# top.net
KiCad netlist of a schematic drawn in Altium Designer
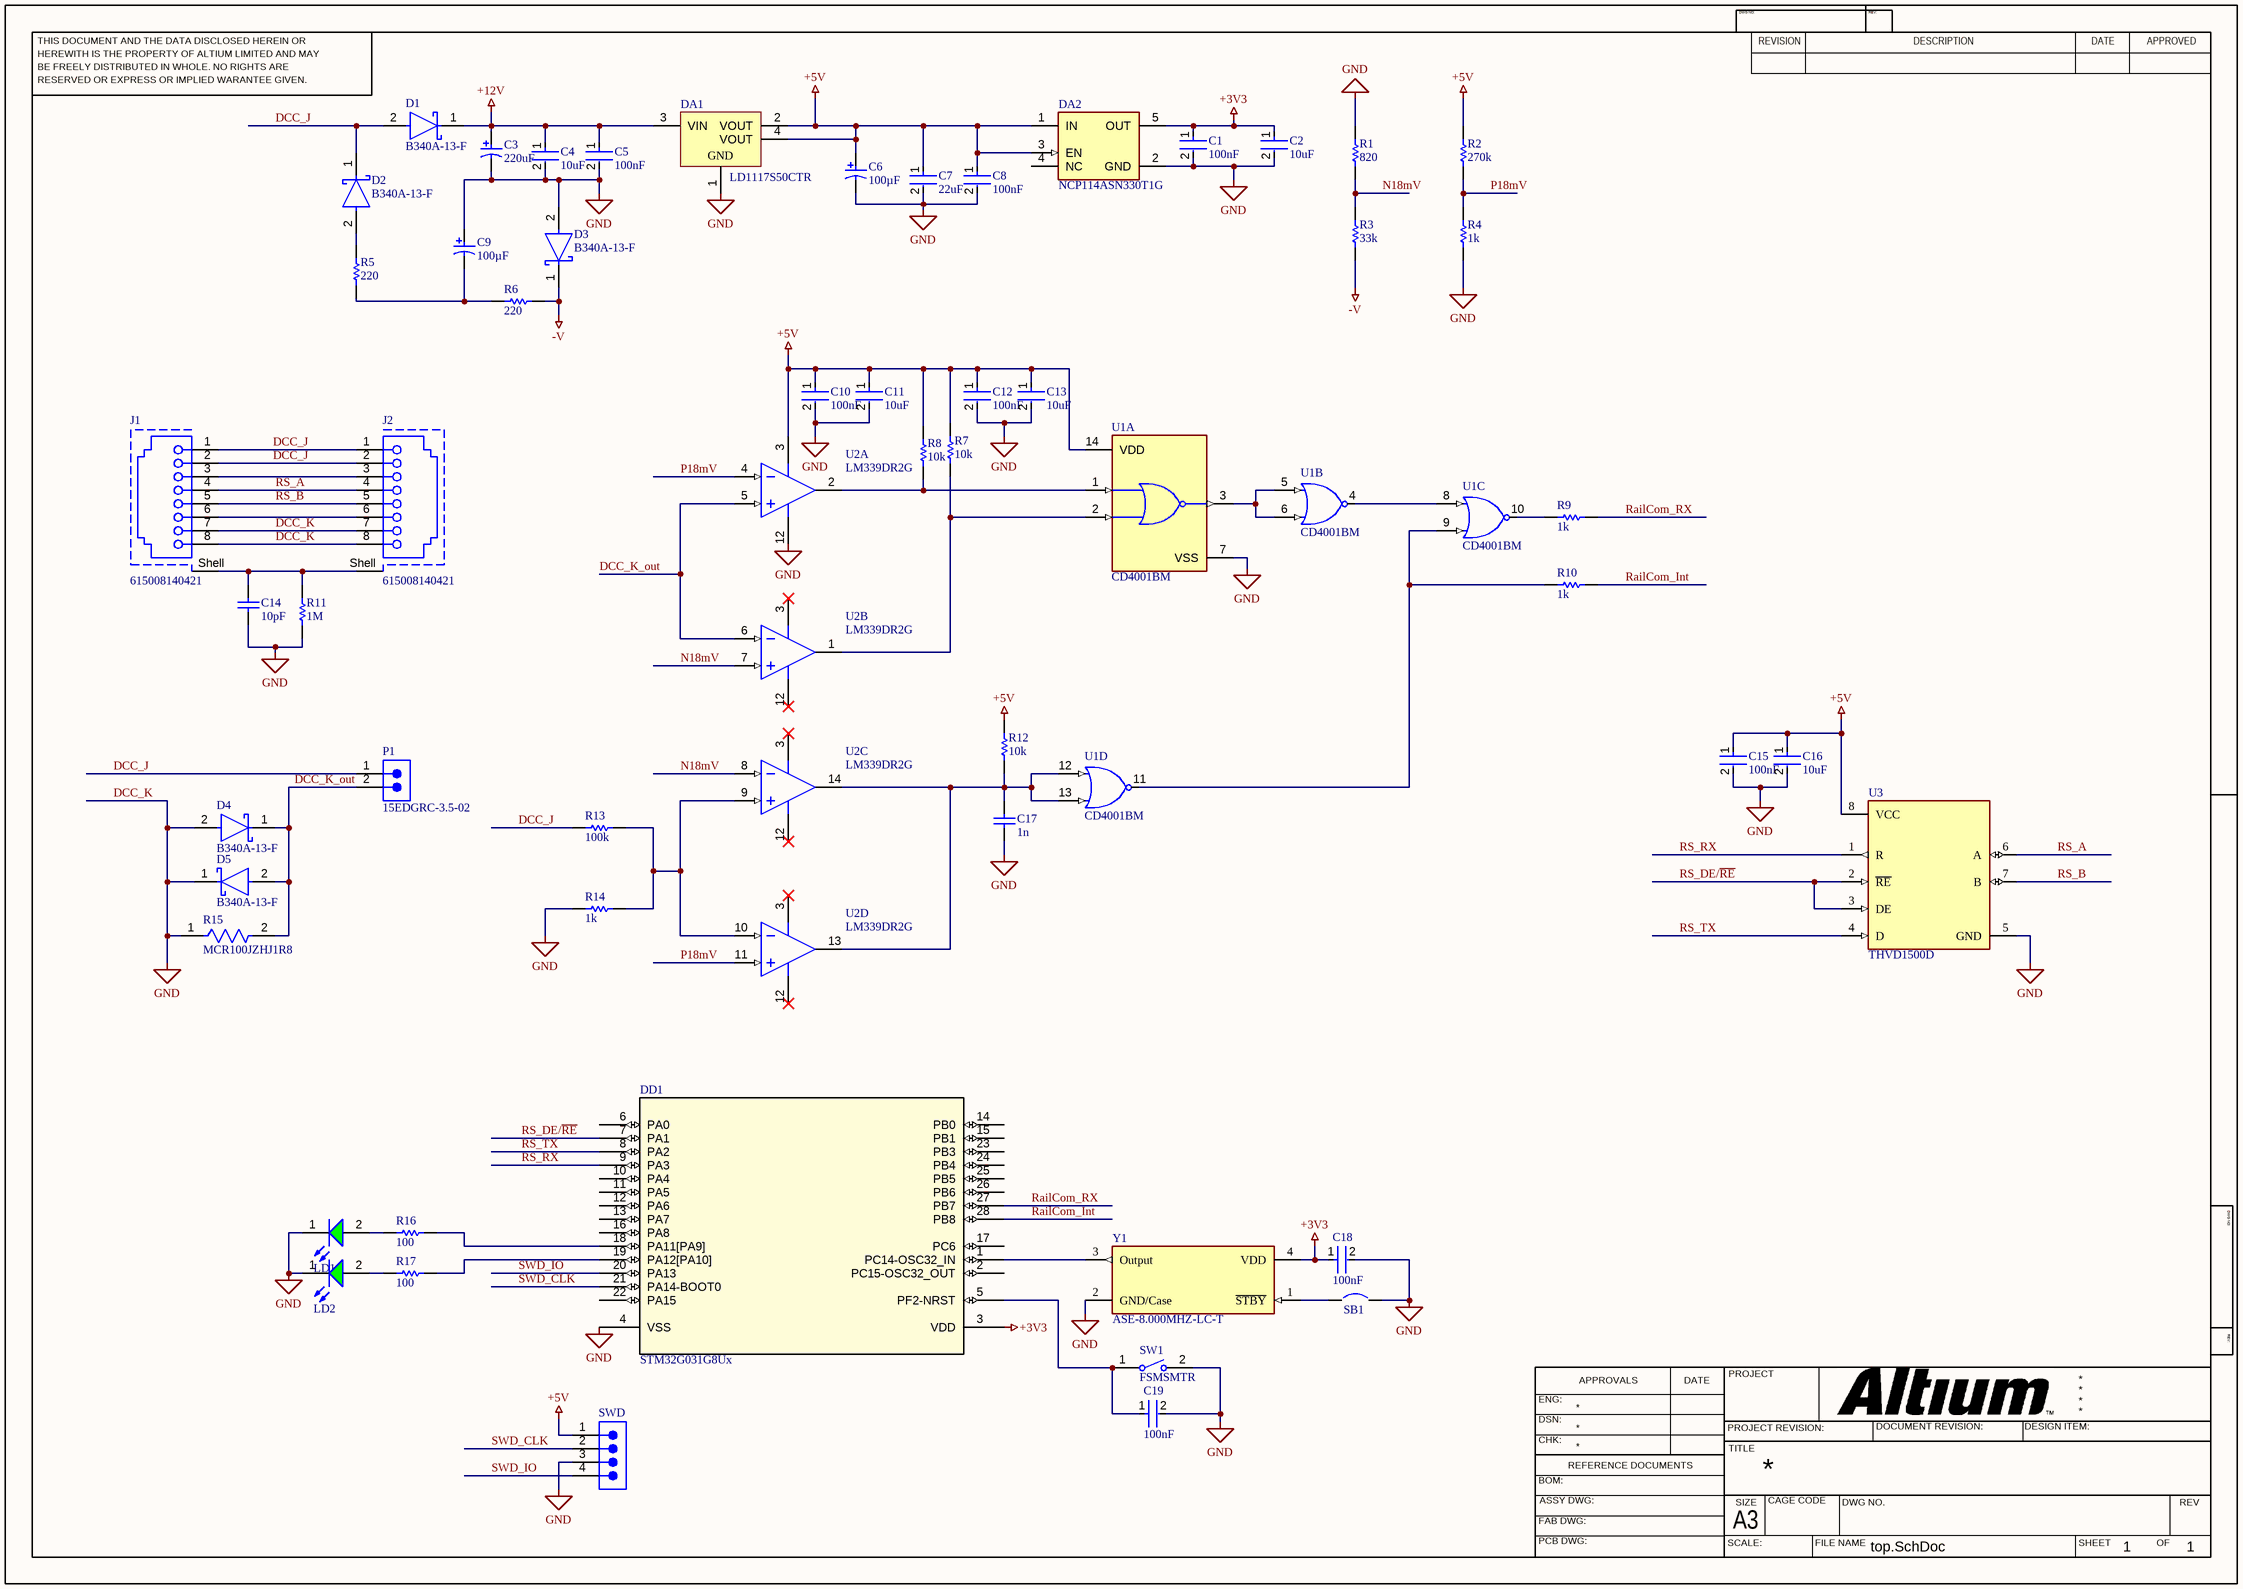
[diagram p0: top.SchDoc]

(export (version "E")
  (design (tool "Eeschema 10.0.6"))
  (components
    (comp (ref "C1")
      (value "CGA3E2X7R1H104K080AA")
      (footprint "FP-CGA3E-0_3-0_1-IPC_C")
      (description "Cap Ceramic 100nF 50V X7R 10% Pad SMD 0603 +125°C Automotive T/R")
      (fields
        (field (name "TOLERANCE") "10%")
        (field (name "CAPACITANCE") "100nF")
        (field (name "VOLTAGE") "50V")
      )
      (libsource (lib "Altium Content Vault") (part "b4654b650e69147ec39a6b967a45e02"))
    )
    (comp (ref "C2")
      (value "GRM188R60J106ME47D")
      (footprint "FP-GRM188-0_1-e0_2_0_55-IPC_C")
      (description "Chip Multilayer Ceramic Capacitors for General Purpose, 0603, 10uF, X5R, 15%, 20%, 6.3V")
      (fields
        (field (name "CAPACITANCE") "10uF")
        (field (name "VOLTAGE") "6.3V")
        (field (name "TOLERANCE") "20%")
      )
      (libsource (lib "Altium Content Vault") (part "02cd4be3c70576c341d710602a673aa"))
    )
    (comp (ref "C3")
      (value "220uF")
      (footprint "PNSC-EEE-FK1E221P_N")
      (fields (field (name "MANUFACTURER") "Panasonic") (field (name "Comment") "EEE-FK1E221P"))
      (libsource (lib "Altium Content Vault") (part "CAP-P-2"))
    )
    (comp (ref "C4")
      (value "GRM188R60J106ME47D")
      (footprint "FP-GRM188-0_1-e0_2_0_55-IPC_C")
      (description "Chip Multilayer Ceramic Capacitors for General Purpose, 0603, 10uF, X5R, 15%, 20%, 6.3V")
      (fields
        (field (name "CAPACITANCE") "10uF")
        (field (name "VOLTAGE") "6.3V")
        (field (name "TOLERANCE") "20%")
      )
      (libsource (lib "Altium Content Vault") (part "02cd4be3c70576c341d710602a673aa"))
    )
    (comp (ref "C5")
      (value "CGA3E2X7R1H104K080AA")
      (footprint "FP-CGA3E-0_3-0_1-IPC_C")
      (description "Cap Ceramic 100nF 50V X7R 10% Pad SMD 0603 +125°C Automotive T/R")
      (fields
        (field (name "TOLERANCE") "10%")
        (field (name "CAPACITANCE") "100nF")
        (field (name "VOLTAGE") "50V")
      )
      (libsource (lib "Altium Content Vault") (part "b4654b650e69147ec39a6b967a45e02"))
    )
    (comp (ref "C6")
      (value "EEEFK1E101XP")
      (footprint "PNSC-FK-V-D8_V")
      (fields (field (name "CAPACITANCE") "100µF") (field (name "MANUFACTURER") "Panasonic"))
      (libsource (lib "Altium Content Vault") (part "CAP-P-2"))
    )
    (comp (ref "C7")
      (value "GRM188R61A226ME15D")
      (footprint "FP-GRM188-0_2-IPC_C")
      (description "Chip Multilayer Ceramic Capacitors for General Purpose, 0603, 22uF, X5R, 15%, 20%, 10V")
      (fields (field (name "TOLERANCE") "20%") (field (name "CAPACITANCE") "22uF"))
      (libsource (lib "Altium Content Vault") (part "11868f565c42a9108669ba33697ecf6"))
    )
    (comp (ref "C8")
      (value "CGA3E2X7R1H104K080AA")
      (footprint "FP-CGA3E-0_3-0_1-IPC_C")
      (description "Cap Ceramic 100nF 50V X7R 10% Pad SMD 0603 +125°C Automotive T/R")
      (fields
        (field (name "TOLERANCE") "10%")
        (field (name "CAPACITANCE") "100nF")
        (field (name "VOLTAGE") "50V")
      )
      (libsource (lib "Altium Content Vault") (part "b4654b650e69147ec39a6b967a45e02"))
    )
    (comp (ref "C9")
      (value "EEEFK1E101XP")
      (footprint "PNSC-FK-V-D8_V")
      (fields (field (name "CAPACITANCE") "100µF") (field (name "MANUFACTURER") "Panasonic"))
      (libsource (lib "Altium Content Vault") (part "CAP-P-2"))
    )
    (comp (ref "C10")
      (value "CGA3E2X7R1H104K080AA")
      (footprint "FP-CGA3E-0_3-0_1-IPC_C")
      (description "Cap Ceramic 100nF 50V X7R 10% Pad SMD 0603 +125°C Automotive T/R")
      (fields
        (field (name "TOLERANCE") "10%")
        (field (name "CAPACITANCE") "100nF")
        (field (name "VOLTAGE") "50V")
      )
      (libsource (lib "Altium Content Vault") (part "b4654b650e69147ec39a6b967a45e02"))
    )
    (comp (ref "C11")
      (value "GRM188R60J106ME47D")
      (footprint "FP-GRM188-0_1-e0_2_0_55-IPC_C")
      (description "Chip Multilayer Ceramic Capacitors for General Purpose, 0603, 10uF, X5R, 15%, 20%, 6.3V")
      (fields
        (field (name "CAPACITANCE") "10uF")
        (field (name "VOLTAGE") "6.3V")
        (field (name "TOLERANCE") "20%")
      )
      (libsource (lib "Altium Content Vault") (part "02cd4be3c70576c341d710602a673aa"))
    )
    (comp (ref "C12")
      (value "CGA3E2X7R1H104K080AA")
      (footprint "FP-CGA3E-0_3-0_1-IPC_C")
      (description "Cap Ceramic 100nF 50V X7R 10% Pad SMD 0603 +125°C Automotive T/R")
      (fields
        (field (name "TOLERANCE") "10%")
        (field (name "CAPACITANCE") "100nF")
        (field (name "VOLTAGE") "50V")
      )
      (libsource (lib "Altium Content Vault") (part "b4654b650e69147ec39a6b967a45e02"))
    )
    (comp (ref "C13")
      (value "GRM188R60J106ME47D")
      (footprint "FP-GRM188-0_1-e0_2_0_55-IPC_C")
      (description "Chip Multilayer Ceramic Capacitors for General Purpose, 0603, 10uF, X5R, 15%, 20%, 6.3V")
      (fields
        (field (name "CAPACITANCE") "10uF")
        (field (name "VOLTAGE") "6.3V")
        (field (name "TOLERANCE") "20%")
      )
      (libsource (lib "Altium Content Vault") (part "02cd4be3c70576c341d710602a673aa"))
    )
    (comp (ref "C14")
      (value "10pF")
      (footprint "CAPC0603(1608)100_N")
      (description "CAP 10pF 25V ±1% 0603 (1608 Metric) Thickness 1mm SMD")
      (fields (field (name "TOLERANCE") "Â±1%") (field (name "Comment") "CAP 10pF 25V 0603(1608)"))
      (libsource (lib "Altium Content Vault") (part "CAP"))
    )
    (comp (ref "C15")
      (value "CGA3E2X7R1H104K080AA")
      (footprint "FP-CGA3E-0_3-0_1-IPC_C")
      (description "Cap Ceramic 100nF 50V X7R 10% Pad SMD 0603 +125°C Automotive T/R")
      (fields
        (field (name "TOLERANCE") "10%")
        (field (name "CAPACITANCE") "100nF")
        (field (name "VOLTAGE") "50V")
      )
      (libsource (lib "Altium Content Vault") (part "b4654b650e69147ec39a6b967a45e02"))
    )
    (comp (ref "C16")
      (value "GRM188R60J106ME47D")
      (footprint "FP-GRM188-0_1-e0_2_0_55-IPC_C")
      (description "Chip Multilayer Ceramic Capacitors for General Purpose, 0603, 10uF, X5R, 15%, 20%, 6.3V")
      (fields
        (field (name "CAPACITANCE") "10uF")
        (field (name "VOLTAGE") "6.3V")
        (field (name "TOLERANCE") "20%")
      )
      (libsource (lib "Altium Content Vault") (part "02cd4be3c70576c341d710602a673aa"))
    )
    (comp (ref "C17")
      (value "1n")
      (footprint "CAPC1608X90X35NL10T15")
      (fields (field (name "PART NUMBER") "GRM188R71H102KA01D") (field (name "MANUFACTURER") "Murata"))
      (libsource (lib "Altium Content Vault") (part "CAP"))
    )
    (comp (ref "C18")
      (value "CGA3E2X7R1H104K080AA")
      (footprint "FP-CGA3E-0_3-0_1-IPC_C")
      (description "Cap Ceramic 100nF 50V X7R 10% Pad SMD 0603 +125°C Automotive T/R")
      (fields
        (field (name "TOLERANCE") "10%")
        (field (name "CAPACITANCE") "100nF")
        (field (name "VOLTAGE") "50V")
      )
      (libsource (lib "Altium Content Vault") (part "b4654b650e69147ec39a6b967a45e02"))
    )
    (comp (ref "C19")
      (value "CGA3E2X7R1H104K080AA")
      (footprint "FP-CGA3E-0_3-0_1-IPC_C")
      (description "Cap Ceramic 100nF 50V X7R 10% Pad SMD 0603 +125°C Automotive T/R")
      (fields
        (field (name "TOLERANCE") "10%")
        (field (name "CAPACITANCE") "100nF")
        (field (name "VOLTAGE") "50V")
      )
      (libsource (lib "Altium Content Vault") (part "b4654b650e69147ec39a6b967a45e02"))
    )
    (comp (ref "D1")
      (value "B340A-13-F")
      (footprint "FP-SMA-MFG")
      (description "DIODE SCHOTTKY 40V 3A SMA")
      (fields (field (name "VOLTAGE") "40V"))
      (libsource (lib "Altium Content Vault") (part "1d6ec82d83fb6aee721767c19dac4b9"))
    )
    (comp (ref "D2")
      (value "B340A-13-F")
      (footprint "FP-SMA-MFG")
      (description "DIODE SCHOTTKY 40V 3A SMA")
      (fields (field (name "VOLTAGE") "40V"))
      (libsource (lib "Altium Content Vault") (part "1d6ec82d83fb6aee721767c19dac4b9"))
    )
    (comp (ref "D3")
      (value "B340A-13-F")
      (footprint "FP-SMA-MFG")
      (description "DIODE SCHOTTKY 40V 3A SMA")
      (fields (field (name "VOLTAGE") "40V"))
      (libsource (lib "Altium Content Vault") (part "1d6ec82d83fb6aee721767c19dac4b9"))
    )
    (comp (ref "D4")
      (value "B340A-13-F")
      (footprint "FP-SMA-MFG")
      (description "DIODE SCHOTTKY 40V 3A SMA")
      (fields (field (name "VOLTAGE") "40V"))
      (libsource (lib "Altium Content Vault") (part "1d6ec82d83fb6aee721767c19dac4b9"))
    )
    (comp (ref "D5")
      (value "B340A-13-F")
      (footprint "FP-SMA-MFG")
      (description "DIODE SCHOTTKY 40V 3A SMA")
      (fields (field (name "VOLTAGE") "40V"))
      (libsource (lib "Altium Content Vault") (part "1d6ec82d83fb6aee721767c19dac4b9"))
    )
    (comp (ref "DA1")
      (value "LD1117S50CTR")
      (footprint "SOT-223_N")
      (description "Fixed Low Drop Positive Voltage Regulator, 5V, 4-Pin SOT-223, Tape and Reel")
      (libsource (lib "Altium Content Vault") (part "PM-REG-LD1117-SOT4"))
    )
    (comp (ref "DA2")
      (value "NCP114ASN330T1G")
      (footprint "FP-483-MFG")
      (description "IC REG LINEAR 3.3V 300MA 5TSOP")
      (fields
        (field (name "MANUFACTURER") "ON Semiconductor")
        (field (name "OCTOPART") "https://octopart.com/ncp114asn330t1g-on+semiconductor-74628742")
      )
      (libsource (lib "Altium Content Vault") (part "57814aa37072aacea77ef0fe9350350"))
    )
    (comp (ref "DD1")
      (value "STM32G031G8Ux")
      (footprint "UFQFPN-28")
      (fields
        (field (name "MANUFACTURER_PART_NUMBER") "stm32g0_ufqfpn28_t1")
        (field (name "COPYRIGHT") "Copyright (C) 2016 Accelerated Designs. All rights reserved")
      )
      (libsource (lib "ST Microelectronics STM32 G0") (part "STM32G031G8Ux"))
    )
    (comp (ref "J1")
      (value "615008140421")
      (footprint "615008140421")
      (libsource (lib "Altium Content Vault") (part "8P8C - 1 Port - Shielded"))
    )
    (comp (ref "J2")
      (value "615008140421")
      (footprint "615008140421")
      (libsource (lib "Altium Content Vault") (part "8P8C - 1 Port - Shielded"))
    )
    (comp (ref "LD1")
      (value "150060VS75000")
      (footprint "WL-SMCW_0603_150060xx75000")
      (description "WURTH ELEKTRONIK - 150060VS75000 - LED, Green, SMD, 0603, 30 mA, 2 V, 570 nm")
      (libsource (lib "Altium Content Vault") (part "LED_Green_2A-1K"))
    )
    (comp (ref "LD2")
      (value "150060VS75000")
      (footprint "WL-SMCW_0603_150060xx75000")
      (description "WURTH ELEKTRONIK - 150060VS75000 - LED, Green, SMD, 0603, 30 mA, 2 V, 570 nm")
      (libsource (lib "Altium Content Vault") (part "LED_Green_2A-1K"))
    )
    (comp (ref "P1")
      (value "15EDGRC-3.5-02")
      (footprint "691305140002")
      (libsource (lib "Altium Content Vault") (part "TBL - 1R - 02P - Male"))
    )
    (comp (ref "R1")
      (value "820")
      (footprint "RESC1608X55X30ML15T15")
      (fields (field (name "MANUFACTURER") "Panasonic") (field (name "PART NUMBER") "ERJ3EKF8203V"))
      (libsource (lib "Altium Content Vault") (part "RES"))
    )
    (comp (ref "R2")
      (value "270k")
      (footprint "RESC0603X26X15LL03T05")
      (fields (field (name "PART NUMBER") "ERJ1GNF2703C") (field (name "MANUFACTURER") "Panasonic"))
      (libsource (lib "Altium Content Vault") (part "RES"))
    )
    (comp (ref "R3")
      (value "33k")
      (footprint "RESC1608X55X30ML20T20")
      (fields (field (name "PART NUMBER") "ERA3AEB333V") (field (name "MANUFACTURER") "Panasonic"))
      (libsource (lib "Altium Content Vault") (part "RES"))
    )
    (comp (ref "R4")
      (value "1k")
      (footprint "RESC1608X55X30NL15T15")
      (fields (field (name "PART NUMBER") "ERJ-3EKF1001V") (field (name "MANUFACTURER") "Panasonic"))
      (libsource (lib "Altium Content Vault") (part "RES"))
    )
    (comp (ref "R5")
      (value "220")
      (footprint "RESC1608X55X30NL15T15")
      (description "Chip Resistor, 220 Ohm, +/- 1%, 0.1 W, -55 to 155 degC, 0603 (1608 Metric), RoHS, Tape and Reel")
      (fields (field (name "TOLERANCE") "1%") (field (name "Comment") "ERJ-3EKF2200V"))
      (libsource (lib "Altium Content Vault") (part "RES-2"))
    )
    (comp (ref "R6")
      (value "220")
      (footprint "RESC1608X55X30NL15T15")
      (description "Chip Resistor, 220 Ohm, +/- 1%, 0.1 W, -55 to 155 degC, 0603 (1608 Metric), RoHS, Tape and Reel")
      (fields (field (name "TOLERANCE") "1%") (field (name "Comment") "ERJ-3EKF2200V"))
      (libsource (lib "Altium Content Vault") (part "RES-2"))
    )
    (comp (ref "R7")
      (value "10k")
      (footprint "RESC1609X55X30NL15T15")
      (description "Chip Resistor, 10 KOhm, +/- 1%, 0.1 W, -55 to 155 degC, 0603 (1608 Metric), RoHS, Tape and Reel")
      (fields (field (name "TOLERANCE") "1%") (field (name "MANUFACTURER") "Panasonic"))
      (libsource (lib "Altium Content Vault") (part "RES-2"))
    )
    (comp (ref "R8")
      (value "10k")
      (footprint "RESC1609X55X30NL15T15")
      (description "Chip Resistor, 10 KOhm, +/- 1%, 0.1 W, -55 to 155 degC, 0603 (1608 Metric), RoHS, Tape and Reel")
      (fields (field (name "TOLERANCE") "1%") (field (name "MANUFACTURER") "Panasonic"))
      (libsource (lib "Altium Content Vault") (part "RES-2"))
    )
    (comp (ref "R9")
      (value "1k")
      (footprint "RESC1608X55X30NL15T15")
      (fields (field (name "PART NUMBER") "ERJ-3EKF1001V") (field (name "MANUFACTURER") "Panasonic"))
      (libsource (lib "Altium Content Vault") (part "RES"))
    )
    (comp (ref "R10")
      (value "1k")
      (footprint "RESC1608X55X30NL15T15")
      (fields (field (name "PART NUMBER") "ERJ-3EKF1001V") (field (name "MANUFACTURER") "Panasonic"))
      (libsource (lib "Altium Content Vault") (part "RES"))
    )
    (comp (ref "R11")
      (value "1M")
      (footprint "RESC1608X55X25LL10T15")
      (description "Chip Resistor, 1 MOhm, +/- 1%, 100 mW, -55 to 155 degC, 0603 (1608 Metric), RoHS, Tape and Reel")
      (fields (field (name "TOLERANCE") "20%") (field (name "Comment") "RC0603FR-071ML"))
      (libsource (lib "Altium Content Vault") (part "RES-2"))
    )
    (comp (ref "R12")
      (value "10k")
      (footprint "RESC1609X55X30NL15T15")
      (description "Chip Resistor, 10 KOhm, +/- 1%, 0.1 W, -55 to 155 degC, 0603 (1608 Metric), RoHS, Tape and Reel")
      (fields (field (name "TOLERANCE") "1%") (field (name "MANUFACTURER") "Panasonic"))
      (libsource (lib "Altium Content Vault") (part "RES-2"))
    )
    (comp (ref "R13")
      (value "100k")
      (footprint "RESC1608X55X30ML15T15")
      (fields (field (name "PART NUMBER") "ERJ-3EKF1003V") (field (name "MANUFACTURER") "Panasonic"))
      (libsource (lib "Altium Content Vault") (part "RES"))
    )
    (comp (ref "R14")
      (value "1k")
      (footprint "RESC1608X55X30NL15T15")
      (fields (field (name "PART NUMBER") "ERJ-3EKF1001V") (field (name "MANUFACTURER") "Panasonic"))
      (libsource (lib "Altium Content Vault") (part "RES"))
    )
    (comp (ref "R15")
      (value "MCR100JZHJ1R8")
      (footprint "FP-MCR100-IPC_C")
      (description "Thick Film Chip Resistor, 2512, 1.8Ω, 5%, +850/+150ppm/°C, 1W, 200V")
      (fields (field (name "TOLERANCE") "5%"))
      (libsource (lib "Altium Content Vault") (part "1029c3af85768c4190bb7ad29bc67b5"))
    )
    (comp (ref "R16")
      (value "100")
      (footprint "RESC1608X55X30NL15T15")
      (fields (field (name "PART NUMBER") "ERJ-3EKF1003V") (field (name "MANUFACTURER") "Panasonic"))
      (libsource (lib "Altium Content Vault") (part "RES"))
    )
    (comp (ref "R17")
      (value "100")
      (footprint "RESC1608X55X30NL15T15")
      (fields (field (name "PART NUMBER") "ERJ-3EKF1003V") (field (name "MANUFACTURER") "Panasonic"))
      (libsource (lib "Altium Content Vault") (part "RES"))
    )
    (comp (ref "SB1")
      (value "~")
      (footprint "JP_SMD")
      (description "Circuit Breaker")
      (fields (field (name "PUBLISHER") "Altium Limited"))
      (libsource (lib "test_adc") (part "Circuit Breaker"))
    )
    (comp (ref "SW1")
      (value "FSMSMTR")
      (footprint "TECO-FSMSMTR_V")
      (description "FSMSM Push Button Switch, 50 mA, -35 to 85 degC, 2-Pin SMD, RoHS, Tape and Reel")
      (fields (field (name "MANUFACTURER") "TE Connectivity"))
      (libsource (lib "Altium Content Vault") (part "SW-SPST-2_C"))
    )
    (comp (ref "SWD")
      (value "61300411121")
      (footprint "61300411121")
      (libsource (lib "Altium Content Vault") (part "Header_Male_1R_04P"))
    )
    (comp (ref "U1")
      (value "CD4001BM")
      (footprint "FP-D0014A-MFG")
      (description "IC GATE NOR 4CH 2-INP 14SOIC")
      (libsource (lib "Altium Content Vault") (part "2cf6dc1d20626fb6062ed3edb113d6e"))
    )
    (comp (ref "U2")
      (value "LM339DR2G")
      (footprint "ONSC-SOIC-14-751A-03_V")
      (description "Single Supply Quad Comparators, 0 to 70 degC, 14-Pin SOIC, Pb-Free, Tape and Reel")
      (fields (field (name "MANUFACTURER") "On Semiconductor"))
      (libsource (lib "Altium Content Vault") (part "ONSC-LM239_LM339_LM2901_NCV2901_MC3302_LMV339-14"))
    )
    (comp (ref "U3")
      (value "THVD1500D")
      (footprint "FP-D0008B-IPC_A")
      (description "IC TRANSCEIVER HALF 1/1 8SOIC")
      (libsource (lib "Altium Content Vault") (part "2959008ed950a7d942df01a48597072"))
    )
    (comp (ref "Y1")
      (value "ASE-8.000MHZ-LC-T")
      (footprint "FP-ASE-MFG")
      (description "XTAL Oscillator 8MHz ±50ppm CMOS 3.3V 4-SMD 3.2mm x 2.5mm")
      (libsource (lib "Altium Content Vault") (part "61a724e6190563596ac712fef61ad37"))
    )
  )
  (nets
    (net (code "1") (name "+3V3") (class "Default")
      (node (ref "C1") (pin "1") (pinfunction "1_1") (pintype "passive"))
      (node (ref "C18") (pin "1") (pinfunction "1_1") (pintype "passive"))
      (node (ref "C2") (pin "1") (pinfunction "1_1") (pintype "passive"))
      (node (ref "DA2") (pin "5") (pinfunction "OUT_5") (pintype "power_in"))
      (node (ref "DD1") (pin "3") (pinfunction "VDD_3") (pintype "power_in"))
      (node (ref "Y1") (pin "4") (pinfunction "VDD_4") (pintype "power_in"))
    )
    (net (code "2") (name "+5V") (class "Default")
      (node (ref "C10") (pin "1") (pinfunction "1_1") (pintype "passive"))
      (node (ref "C11") (pin "1") (pinfunction "1_1") (pintype "passive"))
      (node (ref "C12") (pin "1") (pinfunction "1_1") (pintype "passive"))
      (node (ref "C13") (pin "1") (pinfunction "1_1") (pintype "passive"))
      (node (ref "C15") (pin "1") (pinfunction "1_1") (pintype "passive"))
      (node (ref "C16") (pin "1") (pinfunction "1_1") (pintype "passive"))
      (node (ref "C6") (pin "1") (pinfunction "1_1") (pintype "passive"))
      (node (ref "C7") (pin "1") (pinfunction "1_1") (pintype "passive"))
      (node (ref "C8") (pin "1") (pinfunction "1_1") (pintype "passive"))
      (node (ref "DA1") (pin "2") (pinfunction "VOUT_2") (pintype "power_in"))
      (node (ref "DA1") (pin "4") (pinfunction "VOUT_4") (pintype "power_in"))
      (node (ref "DA2") (pin "1") (pinfunction "IN_1") (pintype "power_in"))
      (node (ref "DA2") (pin "3") (pinfunction "EN_3") (pintype "input"))
      (node (ref "R12") (pin "1") (pinfunction "1_1") (pintype "passive"))
      (node (ref "R2") (pin "2") (pinfunction "2_2") (pintype "passive"))
      (node (ref "R7") (pin "1") (pinfunction "1_1") (pintype "passive"))
      (node (ref "R8") (pin "1") (pinfunction "1_1") (pintype "passive"))
      (node (ref "SWD") (pin "1") (pinfunction "1_1") (pintype "passive"))
      (node (ref "U1") (pin "14") (pinfunction "VDD_14") (pintype "power_in"))
      (node (ref "U2") (pin "3") (pinfunction "VCC_3") (pintype "power_in"))
      (node (ref "U3") (pin "8") (pinfunction "VCC_8") (pintype "power_in"))
    )
    (net (code "3") (name "+12V") (class "Default")
      (node (ref "C3") (pin "1") (pinfunction "1_1") (pintype "passive"))
      (node (ref "C4") (pin "1") (pinfunction "1_1") (pintype "passive"))
      (node (ref "C5") (pin "1") (pinfunction "1_1") (pintype "passive"))
      (node (ref "D1") (pin "1") (pinfunction "C_1") (pintype "passive"))
      (node (ref "DA1") (pin "3") (pinfunction "VIN_3") (pintype "power_in"))
    )
    (net (code "4") (name "-V") (class "Default")
      (node (ref "D3") (pin "1") (pinfunction "C_1") (pintype "passive"))
      (node (ref "R3") (pin "1") (pinfunction "1_1") (pintype "passive"))
      (node (ref "R6") (pin "2") (pinfunction "2_2") (pintype "passive"))
    )
    (net (code "5") (name "/DCC_J") (class "Default")
      (node (ref "D1") (pin "2") (pinfunction "A_2") (pintype "passive"))
      (node (ref "D2") (pin "1") (pinfunction "C_1") (pintype "passive"))
      (node (ref "J1") (pin "1") (pinfunction "1_1") (pintype "passive"))
      (node (ref "J1") (pin "2") (pinfunction "2_2") (pintype "passive"))
      (node (ref "J2") (pin "1") (pinfunction "1_1") (pintype "passive"))
      (node (ref "J2") (pin "2") (pinfunction "2_2") (pintype "passive"))
      (node (ref "P1") (pin "1") (pinfunction "1_1") (pintype "passive"))
      (node (ref "R13") (pin "2") (pinfunction "2_2") (pintype "passive"))
    )
    (net (code "6") (name "/DCC_K_out") (class "Default")
      (node (ref "D4") (pin "1") (pinfunction "C_1") (pintype "passive"))
      (node (ref "D5") (pin "2") (pinfunction "A_2") (pintype "passive"))
      (node (ref "P1") (pin "2") (pinfunction "2_2") (pintype "passive"))
      (node (ref "R15") (pin "2") (pinfunction "2_2") (pintype "passive"))
      (node (ref "U2") (pin "5") (pinfunction "IN1+_5") (pintype "input"))
      (node (ref "U2") (pin "6") (pinfunction "IN2-_6") (pintype "input"))
    )
    (net (code "7") (name "/N18mV") (class "Default")
      (node (ref "R1") (pin "1") (pinfunction "1_1") (pintype "passive"))
      (node (ref "R3") (pin "2") (pinfunction "2_2") (pintype "passive"))
      (node (ref "U2") (pin "7") (pinfunction "IN2+_7") (pintype "input"))
      (node (ref "U2") (pin "8") (pinfunction "IN3-_8") (pintype "input"))
    )
    (net (code "8") (name "/P18mV") (class "Default")
      (node (ref "R2") (pin "1") (pinfunction "1_1") (pintype "passive"))
      (node (ref "R4") (pin "2") (pinfunction "2_2") (pintype "passive"))
      (node (ref "U2") (pin "11") (pinfunction "IN4+_11") (pintype "input"))
      (node (ref "U2") (pin "4") (pinfunction "IN1-_4") (pintype "input"))
    )
    (net (code "9") (name "/RS_A") (class "Default")
      (node (ref "J1") (pin "4") (pinfunction "4_4") (pintype "passive"))
      (node (ref "J2") (pin "4") (pinfunction "4_4") (pintype "passive"))
      (node (ref "U3") (pin "6") (pinfunction "A_6") (pintype "bidirectional"))
    )
    (net (code "10") (name "/RS_B") (class "Default")
      (node (ref "J1") (pin "5") (pinfunction "5_5") (pintype "passive"))
      (node (ref "J2") (pin "5") (pinfunction "5_5") (pintype "passive"))
      (node (ref "U3") (pin "7") (pinfunction "B_7") (pintype "bidirectional"))
    )
    (net (code "11") (name "/RS_DE{slash}~{RE}") (class "Default")
      (node (ref "DD1") (pin "7") (pinfunction "PA1_7") (pintype "bidirectional"))
      (node (ref "U3") (pin "2") (pinfunction "~{RE}_2") (pintype "input"))
      (node (ref "U3") (pin "3") (pinfunction "DE_3") (pintype "input"))
    )
    (net (code "12") (name "/RS_RX") (class "Default")
      (node (ref "DD1") (pin "9") (pinfunction "PA3_9") (pintype "bidirectional"))
      (node (ref "U3") (pin "1") (pinfunction "R_1") (pintype "output"))
    )
    (net (code "13") (name "/RS_TX") (class "Default")
      (node (ref "DD1") (pin "8") (pinfunction "PA2_8") (pintype "bidirectional"))
      (node (ref "U3") (pin "4") (pinfunction "D_4") (pintype "input"))
    )
    (net (code "14") (name "/RailCom_Int") (class "Default")
      (node (ref "DD1") (pin "28") (pinfunction "PB8_28") (pintype "bidirectional"))
      (node (ref "R10") (pin "1") (pinfunction "1_1") (pintype "passive"))
    )
    (net (code "15") (name "/RailCom_RX") (class "Default")
      (node (ref "DD1") (pin "27") (pinfunction "PB7_27") (pintype "bidirectional"))
      (node (ref "R9") (pin "1") (pinfunction "1_1") (pintype "passive"))
    )
    (net (code "16") (name "/SWD_CLK") (class "Default")
      (node (ref "DD1") (pin "21") (pinfunction "PA14-BOOT0_21") (pintype "bidirectional"))
      (node (ref "SWD") (pin "2") (pinfunction "2_2") (pintype "passive"))
    )
    (net (code "17") (name "/SWD_IO") (class "Default")
      (node (ref "DD1") (pin "20") (pinfunction "PA13_20") (pintype "bidirectional"))
      (node (ref "SWD") (pin "4") (pinfunction "4_4") (pintype "passive"))
    )
    (net (code "18") (name "GND") (class "Default")
      (node (ref "C1") (pin "2") (pinfunction "2_2") (pintype "passive"))
      (node (ref "C10") (pin "2") (pinfunction "2_2") (pintype "passive"))
      (node (ref "C11") (pin "2") (pinfunction "2_2") (pintype "passive"))
      (node (ref "C12") (pin "2") (pinfunction "2_2") (pintype "passive"))
      (node (ref "C13") (pin "2") (pinfunction "2_2") (pintype "passive"))
      (node (ref "C14") (pin "2") (pinfunction "2_2") (pintype "passive"))
      (node (ref "C15") (pin "2") (pinfunction "2_2") (pintype "passive"))
      (node (ref "C16") (pin "2") (pinfunction "2_2") (pintype "passive"))
      (node (ref "C17") (pin "1") (pinfunction "1_1") (pintype "passive"))
      (node (ref "C18") (pin "2") (pinfunction "2_2") (pintype "passive"))
      (node (ref "C19") (pin "2") (pinfunction "2_2") (pintype "passive"))
      (node (ref "C2") (pin "2") (pinfunction "2_2") (pintype "passive"))
      (node (ref "C3") (pin "2") (pinfunction "2_2") (pintype "passive"))
      (node (ref "C4") (pin "2") (pinfunction "2_2") (pintype "passive"))
      (node (ref "C5") (pin "2") (pinfunction "2_2") (pintype "passive"))
      (node (ref "C6") (pin "2") (pinfunction "2_2") (pintype "passive"))
      (node (ref "C7") (pin "2") (pinfunction "2_2") (pintype "passive"))
      (node (ref "C8") (pin "2") (pinfunction "2_2") (pintype "passive"))
      (node (ref "C9") (pin "1") (pinfunction "1_1") (pintype "passive"))
      (node (ref "D3") (pin "2") (pinfunction "A_2") (pintype "passive"))
      (node (ref "D4") (pin "2") (pinfunction "A_2") (pintype "passive"))
      (node (ref "D5") (pin "1") (pinfunction "C_1") (pintype "passive"))
      (node (ref "DA1") (pin "1") (pinfunction "GND_1") (pintype "power_in"))
      (node (ref "DA2") (pin "2") (pinfunction "GND_2") (pintype "power_in"))
      (node (ref "DD1") (pin "4") (pinfunction "VSS_4") (pintype "power_in"))
      (node (ref "J1") (pin "7") (pinfunction "7_7") (pintype "passive"))
      (node (ref "J1") (pin "8") (pinfunction "8_8") (pintype "passive"))
      (node (ref "J2") (pin "7") (pinfunction "7_7") (pintype "passive"))
      (node (ref "J2") (pin "8") (pinfunction "8_8") (pintype "passive"))
      (node (ref "LD1") (pin "1") (pinfunction "K_1") (pintype "passive"))
      (node (ref "LD2") (pin "1") (pinfunction "K_1") (pintype "passive"))
      (node (ref "R1") (pin "2") (pinfunction "2_2") (pintype "passive"))
      (node (ref "R11") (pin "2") (pinfunction "2_2") (pintype "passive"))
      (node (ref "R14") (pin "2") (pinfunction "2_2") (pintype "passive"))
      (node (ref "R15") (pin "1") (pinfunction "1_1") (pintype "passive"))
      (node (ref "R4") (pin "1") (pinfunction "1_1") (pintype "passive"))
      (node (ref "SB1") (pin "2") (pinfunction "2_2") (pintype "passive"))
      (node (ref "SW1") (pin "2") (pinfunction "2_2") (pintype "passive"))
      (node (ref "SWD") (pin "3") (pinfunction "3_3") (pintype "passive"))
      (node (ref "U1") (pin "7") (pinfunction "VSS_7") (pintype "power_in"))
      (node (ref "U2") (pin "12") (pinfunction "GND_12") (pintype "power_in"))
      (node (ref "U3") (pin "5") (pinfunction "GND_5") (pintype "power_in"))
      (node (ref "Y1") (pin "2") (pinfunction "GND/Case_2") (pintype "power_in"))
    )
    (net (code "19") (name "Net-(C9-Pad2)") (class "Default")
      (node (ref "C9") (pin "2") (pinfunction "2_2") (pintype "passive"))
      (node (ref "R5") (pin "1") (pinfunction "1_1") (pintype "passive"))
      (node (ref "R6") (pin "1") (pinfunction "1_1") (pintype "passive"))
    )
    (net (code "20") (name "Net-(C14-Pad1)") (class "Default")
      (node (ref "C14") (pin "1") (pinfunction "1_1") (pintype "passive"))
      (node (ref "J1") (pin "Shell") (pinfunction "Shell_Shell") (pintype "passive"))
      (node (ref "J2") (pin "Shell") (pinfunction "Shell_Shell") (pintype "passive"))
      (node (ref "R11") (pin "1") (pinfunction "1_1") (pintype "passive"))
    )
    (net (code "21") (name "Net-(D2-A)") (class "Default")
      (node (ref "D2") (pin "2") (pinfunction "A_2") (pintype "passive"))
      (node (ref "R5") (pin "2") (pinfunction "2_2") (pintype "passive"))
    )
    (net (code "22") (name "Net-(DD1-PA11[PA9])") (class "Default")
      (node (ref "DD1") (pin "18") (pinfunction "PA11[PA9]_18") (pintype "bidirectional"))
      (node (ref "R16") (pin "1") (pinfunction "1_1") (pintype "passive"))
    )
    (net (code "23") (name "Net-(DD1-PA12[PA10])") (class "Default")
      (node (ref "DD1") (pin "19") (pinfunction "PA12[PA10]_19") (pintype "bidirectional"))
      (node (ref "R17") (pin "1") (pinfunction "1_1") (pintype "passive"))
    )
    (net (code "24") (name "Net-(DD1-PC14-OSC32_IN)") (class "Default")
      (node (ref "DD1") (pin "1") (pinfunction "PC14-OSC32_IN_1") (pintype "bidirectional"))
      (node (ref "Y1") (pin "3") (pinfunction "Output_3") (pintype "output"))
    )
    (net (code "25") (name "Net-(DD1-PF2-NRST)") (class "Default")
      (node (ref "C19") (pin "1") (pinfunction "1_1") (pintype "passive"))
      (node (ref "DD1") (pin "5") (pinfunction "PF2-NRST_5") (pintype "bidirectional"))
      (node (ref "SW1") (pin "1") (pinfunction "1_1") (pintype "passive"))
    )
    (net (code "26") (name "Net-(J1-Pad3)") (class "Default")
      (node (ref "J1") (pin "3") (pinfunction "3_3") (pintype "passive"))
      (node (ref "J2") (pin "3") (pinfunction "3_3") (pintype "passive"))
    )
    (net (code "27") (name "Net-(J1-Pad6)") (class "Default")
      (node (ref "J1") (pin "6") (pinfunction "6_6") (pintype "passive"))
      (node (ref "J2") (pin "6") (pinfunction "6_6") (pintype "passive"))
    )
    (net (code "28") (name "Net-(LD1-A)") (class "Default")
      (node (ref "LD1") (pin "2") (pinfunction "A_2") (pintype "passive"))
      (node (ref "R16") (pin "2") (pinfunction "2_2") (pintype "passive"))
    )
    (net (code "29") (name "Net-(LD2-A)") (class "Default")
      (node (ref "LD2") (pin "2") (pinfunction "A_2") (pintype "passive"))
      (node (ref "R17") (pin "2") (pinfunction "2_2") (pintype "passive"))
    )
    (net (code "30") (name "Net-(U1A-A)") (class "Default")
      (node (ref "R8") (pin "2") (pinfunction "2_2") (pintype "passive"))
      (node (ref "U1") (pin "1") (pinfunction "A_1") (pintype "input"))
      (node (ref "U2") (pin "2") (pinfunction "OUT1_2") (pintype "open_collector"))
    )
    (net (code "31") (name "Net-(U1A-B)") (class "Default")
      (node (ref "R7") (pin "2") (pinfunction "2_2") (pintype "passive"))
      (node (ref "U1") (pin "2") (pinfunction "B_2") (pintype "input"))
      (node (ref "U2") (pin "1") (pinfunction "OUT2_1") (pintype "open_collector"))
    )
    (net (code "32") (name "Net-(U1A-J)") (class "Default")
      (node (ref "U1") (pin "3") (pinfunction "J_3") (pintype "output"))
      (node (ref "U1") (pin "5") (pinfunction "C_5") (pintype "input"))
      (node (ref "U1") (pin "6") (pinfunction "D_6") (pintype "input"))
    )
    (net (code "33") (name "Net-(U1B-K)") (class "Default")
      (node (ref "U1") (pin "4") (pinfunction "K_4") (pintype "output"))
      (node (ref "U1") (pin "8") (pinfunction "E_8") (pintype "input"))
    )
    (net (code "34") (name "Net-(U1C-F)") (class "Default")
      (node (ref "R10") (pin "2") (pinfunction "2_2") (pintype "passive"))
      (node (ref "U1") (pin "11") (pinfunction "M_11") (pintype "output"))
      (node (ref "U1") (pin "9") (pinfunction "F_9") (pintype "input"))
    )
    (net (code "35") (name "Net-(U1C-L)") (class "Default")
      (node (ref "R9") (pin "2") (pinfunction "2_2") (pintype "passive"))
      (node (ref "U1") (pin "10") (pinfunction "L_10") (pintype "output"))
    )
    (net (code "36") (name "Net-(U1D-G)") (class "Default")
      (node (ref "C17") (pin "2") (pinfunction "2_2") (pintype "passive"))
      (node (ref "R12") (pin "2") (pinfunction "2_2") (pintype "passive"))
      (node (ref "U1") (pin "12") (pinfunction "G_12") (pintype "input"))
      (node (ref "U1") (pin "13") (pinfunction "H_13") (pintype "input"))
      (node (ref "U2") (pin "13") (pinfunction "OUT4_13") (pintype "open_collector"))
      (node (ref "U2") (pin "14") (pinfunction "OUT3_14") (pintype "open_collector"))
    )
    (net (code "37") (name "Net-(U2C-IN3+)") (class "Default")
      (node (ref "R13") (pin "1") (pinfunction "1_1") (pintype "passive"))
      (node (ref "R14") (pin "1") (pinfunction "1_1") (pintype "passive"))
      (node (ref "U2") (pin "10") (pinfunction "IN4-_10") (pintype "input"))
      (node (ref "U2") (pin "9") (pinfunction "IN3+_9") (pintype "input"))
    )
    (net (code "38") (name "Net-(Y1-~{STBY})") (class "Default")
      (node (ref "SB1") (pin "1") (pinfunction "1_1") (pintype "passive"))
      (node (ref "Y1") (pin "1") (pinfunction "~{STBY}_1") (pintype "input"))
    )
    (net (code "39") (name "unconnected-(DA2-NC-Pad4)") (class "Default")
      (node (ref "DA2") (pin "4") (pinfunction "NC_4") (pintype "passive"))
    )
    (net (code "40") (name "unconnected-(DD1-PA0-Pad6)") (class "Default")
      (node (ref "DD1") (pin "6") (pinfunction "PA0_6") (pintype "bidirectional"))
    )
    (net (code "41") (name "unconnected-(DD1-PA4-Pad10)") (class "Default")
      (node (ref "DD1") (pin "10") (pinfunction "PA4_10") (pintype "bidirectional"))
    )
    (net (code "42") (name "unconnected-(DD1-PA5-Pad11)") (class "Default")
      (node (ref "DD1") (pin "11") (pinfunction "PA5_11") (pintype "bidirectional"))
    )
    (net (code "43") (name "unconnected-(DD1-PA6-Pad12)") (class "Default")
      (node (ref "DD1") (pin "12") (pinfunction "PA6_12") (pintype "bidirectional"))
    )
    (net (code "44") (name "unconnected-(DD1-PA7-Pad13)") (class "Default")
      (node (ref "DD1") (pin "13") (pinfunction "PA7_13") (pintype "bidirectional"))
    )
    (net (code "45") (name "unconnected-(DD1-PA8-Pad16)") (class "Default")
      (node (ref "DD1") (pin "16") (pinfunction "PA8_16") (pintype "bidirectional"))
    )
    (net (code "46") (name "unconnected-(DD1-PA15-Pad22)") (class "Default")
      (node (ref "DD1") (pin "22") (pinfunction "PA15_22") (pintype "bidirectional"))
    )
    (net (code "47") (name "unconnected-(DD1-PB0-Pad14)") (class "Default")
      (node (ref "DD1") (pin "14") (pinfunction "PB0_14") (pintype "bidirectional"))
    )
    (net (code "48") (name "unconnected-(DD1-PB1-Pad15)") (class "Default")
      (node (ref "DD1") (pin "15") (pinfunction "PB1_15") (pintype "bidirectional"))
    )
    (net (code "49") (name "unconnected-(DD1-PB3-Pad23)") (class "Default")
      (node (ref "DD1") (pin "23") (pinfunction "PB3_23") (pintype "bidirectional"))
    )
    (net (code "50") (name "unconnected-(DD1-PB4-Pad24)") (class "Default")
      (node (ref "DD1") (pin "24") (pinfunction "PB4_24") (pintype "bidirectional"))
    )
    (net (code "51") (name "unconnected-(DD1-PB5-Pad25)") (class "Default")
      (node (ref "DD1") (pin "25") (pinfunction "PB5_25") (pintype "bidirectional"))
    )
    (net (code "52") (name "unconnected-(DD1-PB6-Pad26)") (class "Default")
      (node (ref "DD1") (pin "26") (pinfunction "PB6_26") (pintype "bidirectional"))
    )
    (net (code "53") (name "unconnected-(DD1-PC6-Pad17)") (class "Default")
      (node (ref "DD1") (pin "17") (pinfunction "PC6_17") (pintype "bidirectional"))
    )
    (net (code "54") (name "unconnected-(DD1-PC15-OSC32_OUT-Pad2)") (class "Default")
      (node (ref "DD1") (pin "2") (pinfunction "PC15-OSC32_OUT_2") (pintype "bidirectional"))
    )
    (net (code "55") (name "unconnected-(U2B-GND-Pad12)") (class "Default")
      (node (ref "U2") (pin "12") (pinfunction "GND_12") (pintype "power_in+no_connect"))
    )
    (net (code "56") (name "unconnected-(U2B-VCC-Pad3)") (class "Default")
      (node (ref "U2") (pin "3") (pinfunction "VCC_3") (pintype "power_in+no_connect"))
    )
    (net (code "57") (name "unconnected-(U2C-GND-Pad12)") (class "Default")
      (node (ref "U2") (pin "12") (pinfunction "GND_12") (pintype "power_in+no_connect"))
    )
    (net (code "58") (name "unconnected-(U2C-VCC-Pad3)") (class "Default")
      (node (ref "U2") (pin "3") (pinfunction "VCC_3") (pintype "power_in+no_connect"))
    )
    (net (code "59") (name "unconnected-(U2D-GND-Pad12)") (class "Default")
      (node (ref "U2") (pin "12") (pinfunction "GND_12") (pintype "power_in+no_connect"))
    )
    (net (code "60") (name "unconnected-(U2D-VCC-Pad3)") (class "Default")
      (node (ref "U2") (pin "3") (pinfunction "VCC_3") (pintype "power_in+no_connect"))
    )
  )
)
